# Peripherals.net
KiCad netlist of a schematic drawn in Altium Designer
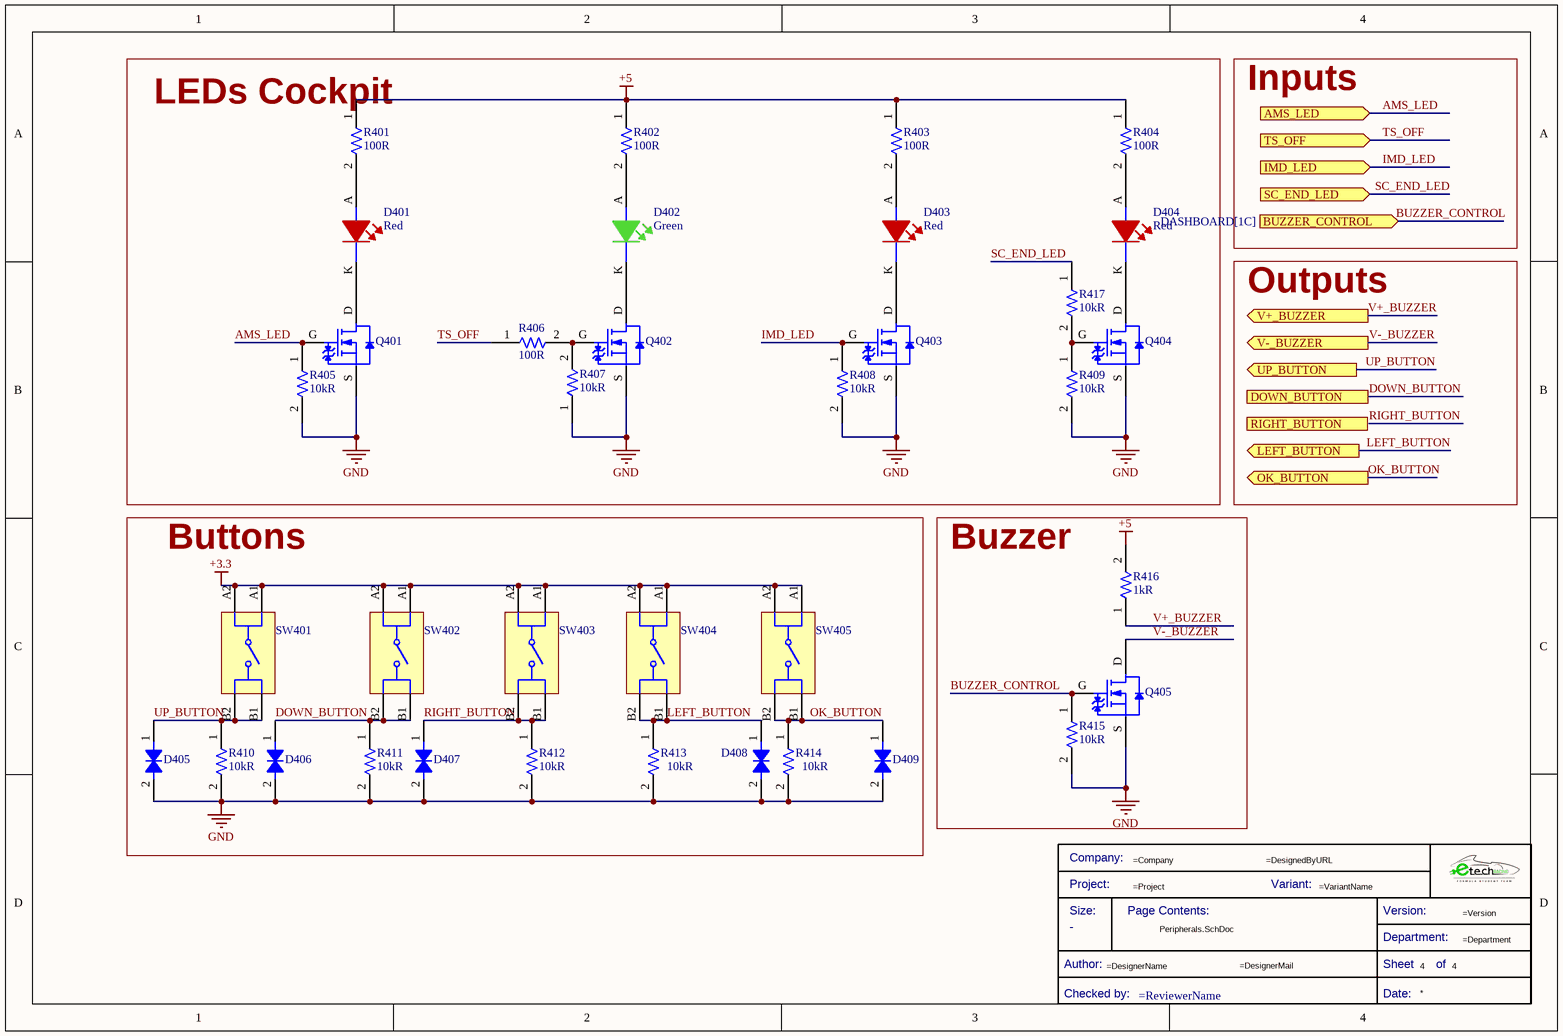
[diagram p0: Peripherals.SchDoc]

(export (version "E")
  (design (tool "Eeschema 10.0.6"))
  (components
    (comp (ref "D401")
      (value "150080RS75000")
      (footprint "LED-THT/WE/D3.9H10.5")
      (description "0805(H=0.8mm) 红色 高亮 λD=625nm VF=2V IF=30mA PD=72mW")
      (fields (field (name "COLOR") "Red") (field (name ".CREATOR") "DR"))
      (libsource (lib "Semiconductor") (part "LEDRS-THT"))
    )
    (comp (ref "D402")
      (value "150080GS75000")
      (footprint "LED-THT/WE/D3.9H10.5")
      (description "Led, Green, 520 Nm, 3.2 V, 30 Ma, 450 Mcd Rohs Compliant: Yes")
      (fields (field (name "COLOR") "Green") (field (name ".CREATOR") "GP"))
      (libsource (lib "Semiconductor") (part "LEDGS-THT"))
    )
    (comp (ref "D403")
      (value "150080RS75000")
      (footprint "LED-THT/WE/D3.9H10.5")
      (description "0805(H=0.8mm) 红色 高亮 λD=625nm VF=2V IF=30mA PD=72mW")
      (fields (field (name "COLOR") "Red") (field (name ".CREATOR") "DR"))
      (libsource (lib "Semiconductor") (part "LEDRS-THT"))
    )
    (comp (ref "D404")
      (value "150080RS75000")
      (footprint "LED-THT/WE/D3.9H10.5")
      (description "0805(H=0.8mm) 红色 高亮 λD=625nm VF=2V IF=30mA PD=72mW")
      (fields (field (name "COLOR") "Red") (field (name ".CREATOR") "DR"))
      (libsource (lib "Semiconductor") (part "LEDRS-THT"))
    )
    (comp (ref "D405")
      (value "824501600")
      (footprint "DTVS-DO-214AC")
      (description "TVS diode [Würth Elektronik] 824501600 TVS diode")
      (fields (field (name "MANUFACTURER") "Wurth Electronics") (field (name ".CREATOR") "DO"))
      (libsource (lib "Filter components") (part "DTVS-6V-DO-214AC"))
    )
    (comp (ref "D406")
      (value "824501600")
      (footprint "DTVS-DO-214AC")
      (description "TVS diode [Würth Elektronik] 824501600 TVS diode")
      (fields (field (name "MANUFACTURER") "Wurth Electronics") (field (name ".CREATOR") "DO"))
      (libsource (lib "Filter components") (part "DTVS-6V-DO-214AC"))
    )
    (comp (ref "D407")
      (value "824501600")
      (footprint "DTVS-DO-214AC")
      (description "TVS diode [Würth Elektronik] 824501600 TVS diode")
      (fields (field (name "MANUFACTURER") "Wurth Electronics") (field (name ".CREATOR") "DO"))
      (libsource (lib "Filter components") (part "DTVS-6V-DO-214AC"))
    )
    (comp (ref "D408")
      (value "824501600")
      (footprint "DTVS-DO-214AC")
      (description "TVS diode [Würth Elektronik] 824501600 TVS diode")
      (fields (field (name "MANUFACTURER") "Wurth Electronics") (field (name ".CREATOR") "DO"))
      (libsource (lib "Filter components") (part "DTVS-6V-DO-214AC"))
    )
    (comp (ref "D409")
      (value "824501600")
      (footprint "DTVS-DO-214AC")
      (description "TVS diode [Würth Elektronik] 824501600 TVS diode")
      (fields (field (name "MANUFACTURER") "Wurth Electronics") (field (name ".CREATOR") "DO"))
      (libsource (lib "Filter components") (part "DTVS-6V-DO-214AC"))
    )
    (comp (ref "Q401")
      (value "SQ2318BES-T1_GE3")
      (footprint "TRT-NCH-3/35-CPH")
      (description "Automotive N-channel 40 V (d-s) 175C Mosfet SOT-23")
      (fields (field (name ".CREATOR") "DO"))
      (libsource (lib "Semiconductor") (part "TRT-NCH-8/40-SQ"))
    )
    (comp (ref "Q402")
      (value "SQ2318BES-T1_GE3")
      (footprint "TRT-NCH-3/35-CPH")
      (description "Automotive N-channel 40 V (d-s) 175C Mosfet SOT-23")
      (fields (field (name ".CREATOR") "DO"))
      (libsource (lib "Semiconductor") (part "TRT-NCH-8/40-SQ"))
    )
    (comp (ref "Q403")
      (value "SQ2318BES-T1_GE3")
      (footprint "TRT-NCH-3/35-CPH")
      (description "Automotive N-channel 40 V (d-s) 175C Mosfet SOT-23")
      (fields (field (name ".CREATOR") "DO"))
      (libsource (lib "Semiconductor") (part "TRT-NCH-8/40-SQ"))
    )
    (comp (ref "Q404")
      (value "SQ2318BES-T1_GE3")
      (footprint "TRT-NCH-3/35-CPH")
      (description "Automotive N-channel 40 V (d-s) 175C Mosfet SOT-23")
      (fields (field (name ".CREATOR") "DO"))
      (libsource (lib "Semiconductor") (part "TRT-NCH-8/40-SQ"))
    )
    (comp (ref "Q405")
      (value "SQ2318BES-T1_GE3")
      (footprint "TRT-NCH-3/35-CPH")
      (description "Automotive N-channel 40 V (d-s) 175C Mosfet SOT-23")
      (fields (field (name ".CREATOR") "DO"))
      (libsource (lib "Semiconductor") (part "TRT-NCH-8/40-SQ"))
    )
    (comp (ref "R401")
      (value "CR0805-FX-1000ELF")
      (footprint "R0805FTK")
      (description "Res Thick Film 0805 100 Ohm 1% 1/8W ±100ppm/°C Molded SMD SMD Paper Tape on Plastic Reel")
      (fields
        (field (name "TOLERANCE") "1%")
        (field (name "RESISTANCE") "100R")
        (field (name ".CREATOR") "DR")
      )
      (libsource (lib "Passives") (part "R100-0805FTK"))
    )
    (comp (ref "R402")
      (value "CR0805-FX-1000ELF")
      (footprint "R0805FTK")
      (description "Res Thick Film 0805 100 Ohm 1% 1/8W ±100ppm/°C Molded SMD SMD Paper Tape on Plastic Reel")
      (fields
        (field (name "TOLERANCE") "1%")
        (field (name "RESISTANCE") "100R")
        (field (name ".CREATOR") "DR")
      )
      (libsource (lib "Passives") (part "R100-0805FTK"))
    )
    (comp (ref "R403")
      (value "CR0805-FX-1000ELF")
      (footprint "R0805FTK")
      (description "Res Thick Film 0805 100 Ohm 1% 1/8W ±100ppm/°C Molded SMD SMD Paper Tape on Plastic Reel")
      (fields
        (field (name "TOLERANCE") "1%")
        (field (name "RESISTANCE") "100R")
        (field (name ".CREATOR") "DR")
      )
      (libsource (lib "Passives") (part "R100-0805FTK"))
    )
    (comp (ref "R404")
      (value "CR0805-FX-1000ELF")
      (footprint "R0805FTK")
      (description "Res Thick Film 0805 100 Ohm 1% 1/8W ±100ppm/°C Molded SMD SMD Paper Tape on Plastic Reel")
      (fields
        (field (name "TOLERANCE") "1%")
        (field (name "RESISTANCE") "100R")
        (field (name ".CREATOR") "DR")
      )
      (libsource (lib "Passives") (part "R100-0805FTK"))
    )
    (comp (ref "R405")
      (value "CR0805-JW-103ELF")
      (footprint "R0805FTK")
      (fields
        (field (name "TOLERANCE") "5%")
        (field (name "RESISTANCE") "10kR")
        (field (name ".CREATOR") "DR")
      )
      (libsource (lib "Passives") (part "R10k-0805FTK"))
    )
    (comp (ref "R406")
      (value "CR0805-FX-1000ELF")
      (footprint "R0805FTK")
      (description "Res Thick Film 0805 100 Ohm 1% 1/8W ±100ppm/°C Molded SMD SMD Paper Tape on Plastic Reel")
      (fields
        (field (name "TOLERANCE") "1%")
        (field (name "RESISTANCE") "100R")
        (field (name ".CREATOR") "DR")
      )
      (libsource (lib "Passives") (part "R100-0805FTK"))
    )
    (comp (ref "R407")
      (value "CR0805-JW-103ELF")
      (footprint "R0805FTK")
      (fields
        (field (name "TOLERANCE") "5%")
        (field (name "RESISTANCE") "10kR")
        (field (name ".CREATOR") "DR")
      )
      (libsource (lib "Passives") (part "R10k-0805FTK"))
    )
    (comp (ref "R408")
      (value "CR0805-JW-103ELF")
      (footprint "R0805FTK")
      (fields
        (field (name "TOLERANCE") "5%")
        (field (name "RESISTANCE") "10kR")
        (field (name ".CREATOR") "DR")
      )
      (libsource (lib "Passives") (part "R10k-0805FTK"))
    )
    (comp (ref "R409")
      (value "CR0805-JW-103ELF")
      (footprint "R0805FTK")
      (fields
        (field (name "TOLERANCE") "5%")
        (field (name "RESISTANCE") "10kR")
        (field (name ".CREATOR") "DR")
      )
      (libsource (lib "Passives") (part "R10k-0805FTK"))
    )
    (comp (ref "R410")
      (value "CR0805-JW-103ELF")
      (footprint "R0805FTK")
      (fields
        (field (name "TOLERANCE") "5%")
        (field (name "RESISTANCE") "10kR")
        (field (name ".CREATOR") "DR")
      )
      (libsource (lib "Passives") (part "R10k-0805FTK"))
    )
    (comp (ref "R411")
      (value "CR0805-JW-103ELF")
      (footprint "R0805FTK")
      (fields
        (field (name "TOLERANCE") "5%")
        (field (name "RESISTANCE") "10kR")
        (field (name ".CREATOR") "DR")
      )
      (libsource (lib "Passives") (part "R10k-0805FTK"))
    )
    (comp (ref "R412")
      (value "CR0805-JW-103ELF")
      (footprint "R0805FTK")
      (fields
        (field (name "TOLERANCE") "5%")
        (field (name "RESISTANCE") "10kR")
        (field (name ".CREATOR") "DR")
      )
      (libsource (lib "Passives") (part "R10k-0805FTK"))
    )
    (comp (ref "R413")
      (value "CR0805-JW-103ELF")
      (footprint "R0805FTK")
      (fields
        (field (name "TOLERANCE") "5%")
        (field (name "RESISTANCE") "10kR")
        (field (name ".CREATOR") "DR")
      )
      (libsource (lib "Passives") (part "R10k-0805FTK"))
    )
    (comp (ref "R414")
      (value "CR0805-JW-103ELF")
      (footprint "R0805FTK")
      (fields
        (field (name "TOLERANCE") "5%")
        (field (name "RESISTANCE") "10kR")
        (field (name ".CREATOR") "DR")
      )
      (libsource (lib "Passives") (part "R10k-0805FTK"))
    )
    (comp (ref "R415")
      (value "CR0805-JW-103ELF")
      (footprint "R0805FTK")
      (fields
        (field (name "TOLERANCE") "5%")
        (field (name "RESISTANCE") "10kR")
        (field (name ".CREATOR") "DR")
      )
      (libsource (lib "Passives") (part "R10k-0805FTK"))
    )
    (comp (ref "R416")
      (value "CR0805-JW-102ELF")
      (footprint "R0805FTK")
      (description "Res Thick Film 0805 1K Ohm 5% 1/8W ±200ppm/°C Molded SMD SMD Paper Tape on Plastic Reel")
      (fields
        (field (name "TOLERANCE") "5%")
        (field (name "RESISTANCE") "1kR")
        (field (name ".CREATOR") "GP")
      )
      (libsource (lib "Passives") (part "R1k-0805FTK"))
    )
    (comp (ref "R417")
      (value "CR0805-JW-104ELF")
      (footprint "R0805FTK")
      (fields
        (field (name "TOLERANCE") "5%")
        (field (name "RESISTANCE") "10kR")
        (field (name ".CREATOR") "DR")
      )
      (libsource (lib "Passives") (part "R10k-0805FTK"))
    )
    (comp (ref "SW401")
      (value "430456073736")
      (footprint "SWITCH_12x12/4304x60737x6")
      (description "WS-TATV THT Washable Tact Switch 12x12mm, SPST-NO, 12VDC, 50mA, 360g")
      (libsource (lib "Electromechanical") (part "Switch_THT_NO/430456073736"))
    )
    (comp (ref "SW402")
      (value "430456073736")
      (footprint "SWITCH_12x12/4304x60737x6")
      (description "WS-TATV THT Washable Tact Switch 12x12mm, SPST-NO, 12VDC, 50mA, 360g")
      (libsource (lib "Electromechanical") (part "Switch_THT_NO/430456073736"))
    )
    (comp (ref "SW403")
      (value "430456073736")
      (footprint "SWITCH_12x12/4304x60737x6")
      (description "WS-TATV THT Washable Tact Switch 12x12mm, SPST-NO, 12VDC, 50mA, 360g")
      (libsource (lib "Electromechanical") (part "Switch_THT_NO/430456073736"))
    )
    (comp (ref "SW404")
      (value "430456073736")
      (footprint "SWITCH_12x12/4304x60737x6")
      (description "WS-TATV THT Washable Tact Switch 12x12mm, SPST-NO, 12VDC, 50mA, 360g")
      (libsource (lib "Electromechanical") (part "Switch_THT_NO/430456073736"))
    )
    (comp (ref "SW405")
      (value "430456073736")
      (footprint "SWITCH_12x12/4304x60737x6")
      (description "WS-TATV THT Washable Tact Switch 12x12mm, SPST-NO, 12VDC, 50mA, 360g")
      (libsource (lib "Electromechanical") (part "Switch_THT_NO/430456073736"))
    )
  )
  (nets
    (net (code "1") (name "+3.3") (class "Default")
      (node (ref "SW401") (pin "A1") (pinfunction "A1_A1") (pintype "passive"))
      (node (ref "SW401") (pin "A2") (pinfunction "A2_A2") (pintype "passive"))
      (node (ref "SW402") (pin "A1") (pinfunction "A1_A1") (pintype "passive"))
      (node (ref "SW402") (pin "A2") (pinfunction "A2_A2") (pintype "passive"))
      (node (ref "SW403") (pin "A1") (pinfunction "A1_A1") (pintype "passive"))
      (node (ref "SW403") (pin "A2") (pinfunction "A2_A2") (pintype "passive"))
      (node (ref "SW404") (pin "A1") (pinfunction "A1_A1") (pintype "passive"))
      (node (ref "SW404") (pin "A2") (pinfunction "A2_A2") (pintype "passive"))
      (node (ref "SW405") (pin "A1") (pinfunction "A1_A1") (pintype "passive"))
      (node (ref "SW405") (pin "A2") (pinfunction "A2_A2") (pintype "passive"))
    )
    (net (code "2") (name "+5") (class "Default")
      (node (ref "R401") (pin "1") (pinfunction "1_1") (pintype "passive"))
      (node (ref "R402") (pin "1") (pinfunction "1_1") (pintype "passive"))
      (node (ref "R403") (pin "1") (pinfunction "1_1") (pintype "passive"))
      (node (ref "R404") (pin "1") (pinfunction "1_1") (pintype "passive"))
      (node (ref "R416") (pin "2") (pinfunction "2_2") (pintype "passive"))
    )
    (net (code "3") (name "/AMS_LED") (class "Default")
      (node (ref "Q401") (pin "G") (pinfunction "G_G") (pintype "passive"))
      (node (ref "R405") (pin "1") (pinfunction "1_1") (pintype "passive"))
    )
    (net (code "4") (name "/BUZZER_CONTROL") (class "Default")
      (node (ref "Q405") (pin "G") (pinfunction "G_G") (pintype "passive"))
      (node (ref "R415") (pin "1") (pinfunction "1_1") (pintype "passive"))
    )
    (net (code "5") (name "/DOWN_BUTTON") (class "Default")
      (node (ref "D406") (pin "1") (pinfunction "1_1") (pintype "passive"))
      (node (ref "R411") (pin "1") (pinfunction "1_1") (pintype "passive"))
      (node (ref "SW402") (pin "B1") (pinfunction "B1_B1") (pintype "passive"))
      (node (ref "SW402") (pin "B2") (pinfunction "B2_B2") (pintype "passive"))
    )
    (net (code "6") (name "/IMD_LED") (class "Default")
      (node (ref "Q403") (pin "G") (pinfunction "G_G") (pintype "passive"))
      (node (ref "R408") (pin "1") (pinfunction "1_1") (pintype "passive"))
    )
    (net (code "7") (name "/LEFT_BUTTON") (class "Default")
      (node (ref "D408") (pin "1") (pinfunction "1_1") (pintype "passive"))
      (node (ref "R413") (pin "1") (pinfunction "1_1") (pintype "passive"))
      (node (ref "SW404") (pin "B1") (pinfunction "B1_B1") (pintype "passive"))
      (node (ref "SW404") (pin "B2") (pinfunction "B2_B2") (pintype "passive"))
    )
    (net (code "8") (name "/OK_BUTTON") (class "Default")
      (node (ref "D409") (pin "1") (pinfunction "1_1") (pintype "passive"))
      (node (ref "R414") (pin "1") (pinfunction "1_1") (pintype "passive"))
      (node (ref "SW405") (pin "B1") (pinfunction "B1_B1") (pintype "passive"))
      (node (ref "SW405") (pin "B2") (pinfunction "B2_B2") (pintype "passive"))
    )
    (net (code "9") (name "/RIGHT_BUTTON") (class "Default")
      (node (ref "D407") (pin "1") (pinfunction "1_1") (pintype "passive"))
      (node (ref "R412") (pin "1") (pinfunction "1_1") (pintype "passive"))
      (node (ref "SW403") (pin "B1") (pinfunction "B1_B1") (pintype "passive"))
      (node (ref "SW403") (pin "B2") (pinfunction "B2_B2") (pintype "passive"))
    )
    (net (code "10") (name "/SC_END_LED") (class "Default")
      (node (ref "R417") (pin "1") (pinfunction "1_1") (pintype "passive"))
    )
    (net (code "11") (name "/TS_OFF") (class "Default")
      (node (ref "R406") (pin "1") (pinfunction "1_1") (pintype "passive"))
    )
    (net (code "12") (name "/UP_BUTTON") (class "Default")
      (node (ref "D405") (pin "1") (pinfunction "1_1") (pintype "passive"))
      (node (ref "R410") (pin "1") (pinfunction "1_1") (pintype "passive"))
      (node (ref "SW401") (pin "B1") (pinfunction "B1_B1") (pintype "passive"))
      (node (ref "SW401") (pin "B2") (pinfunction "B2_B2") (pintype "passive"))
    )
    (net (code "13") (name "/V+_BUZZER") (class "Default")
      (node (ref "R416") (pin "1") (pinfunction "1_1") (pintype "passive"))
    )
    (net (code "14") (name "/V-_BUZZER") (class "Default")
      (node (ref "Q405") (pin "D") (pinfunction "D_D") (pintype "passive"))
    )
    (net (code "15") (name "GND") (class "Default")
      (node (ref "D405") (pin "2") (pinfunction "2_2") (pintype "passive"))
      (node (ref "D406") (pin "2") (pinfunction "2_2") (pintype "passive"))
      (node (ref "D407") (pin "2") (pinfunction "2_2") (pintype "passive"))
      (node (ref "D408") (pin "2") (pinfunction "2_2") (pintype "passive"))
      (node (ref "D409") (pin "2") (pinfunction "2_2") (pintype "passive"))
      (node (ref "Q401") (pin "S") (pinfunction "S_S") (pintype "passive"))
      (node (ref "Q402") (pin "S") (pinfunction "S_S") (pintype "passive"))
      (node (ref "Q403") (pin "S") (pinfunction "S_S") (pintype "passive"))
      (node (ref "Q404") (pin "S") (pinfunction "S_S") (pintype "passive"))
      (node (ref "Q405") (pin "S") (pinfunction "S_S") (pintype "passive"))
      (node (ref "R405") (pin "2") (pinfunction "2_2") (pintype "passive"))
      (node (ref "R407") (pin "1") (pinfunction "1_1") (pintype "passive"))
      (node (ref "R408") (pin "2") (pinfunction "2_2") (pintype "passive"))
      (node (ref "R409") (pin "2") (pinfunction "2_2") (pintype "passive"))
      (node (ref "R410") (pin "2") (pinfunction "2_2") (pintype "passive"))
      (node (ref "R411") (pin "2") (pinfunction "2_2") (pintype "passive"))
      (node (ref "R412") (pin "2") (pinfunction "2_2") (pintype "passive"))
      (node (ref "R413") (pin "2") (pinfunction "2_2") (pintype "passive"))
      (node (ref "R414") (pin "2") (pinfunction "2_2") (pintype "passive"))
      (node (ref "R415") (pin "2") (pinfunction "2_2") (pintype "passive"))
    )
    (net (code "16") (name "Net-(D401-PadA)") (class "Default")
      (node (ref "D401") (pin "A") (pinfunction "A_A") (pintype "passive"))
      (node (ref "R401") (pin "2") (pinfunction "2_2") (pintype "passive"))
    )
    (net (code "17") (name "Net-(D401-PadK)") (class "Default")
      (node (ref "D401") (pin "K") (pinfunction "K_K") (pintype "passive"))
      (node (ref "Q401") (pin "D") (pinfunction "D_D") (pintype "passive"))
    )
    (net (code "18") (name "Net-(D402-PadA)") (class "Default")
      (node (ref "D402") (pin "A") (pinfunction "A_A") (pintype "passive"))
      (node (ref "R402") (pin "2") (pinfunction "2_2") (pintype "passive"))
    )
    (net (code "19") (name "Net-(D402-PadK)") (class "Default")
      (node (ref "D402") (pin "K") (pinfunction "K_K") (pintype "passive"))
      (node (ref "Q402") (pin "D") (pinfunction "D_D") (pintype "passive"))
    )
    (net (code "20") (name "Net-(D403-PadA)") (class "Default")
      (node (ref "D403") (pin "A") (pinfunction "A_A") (pintype "passive"))
      (node (ref "R403") (pin "2") (pinfunction "2_2") (pintype "passive"))
    )
    (net (code "21") (name "Net-(D403-PadK)") (class "Default")
      (node (ref "D403") (pin "K") (pinfunction "K_K") (pintype "passive"))
      (node (ref "Q403") (pin "D") (pinfunction "D_D") (pintype "passive"))
    )
    (net (code "22") (name "Net-(D404-PadA)") (class "Default")
      (node (ref "D404") (pin "A") (pinfunction "A_A") (pintype "passive"))
      (node (ref "R404") (pin "2") (pinfunction "2_2") (pintype "passive"))
    )
    (net (code "23") (name "Net-(D404-PadK)") (class "Default")
      (node (ref "D404") (pin "K") (pinfunction "K_K") (pintype "passive"))
      (node (ref "Q404") (pin "D") (pinfunction "D_D") (pintype "passive"))
    )
    (net (code "24") (name "Net-(Q402-PadG)") (class "Default")
      (node (ref "Q402") (pin "G") (pinfunction "G_G") (pintype "passive"))
      (node (ref "R406") (pin "2") (pinfunction "2_2") (pintype "passive"))
      (node (ref "R407") (pin "2") (pinfunction "2_2") (pintype "passive"))
    )
    (net (code "25") (name "Net-(Q404-PadG)") (class "Default")
      (node (ref "Q404") (pin "G") (pinfunction "G_G") (pintype "passive"))
      (node (ref "R409") (pin "1") (pinfunction "1_1") (pintype "passive"))
      (node (ref "R417") (pin "2") (pinfunction "2_2") (pintype "passive"))
    )
  )
)
